# 3v3Regulator.net
KiCad netlist of a schematic drawn in Altium Designer
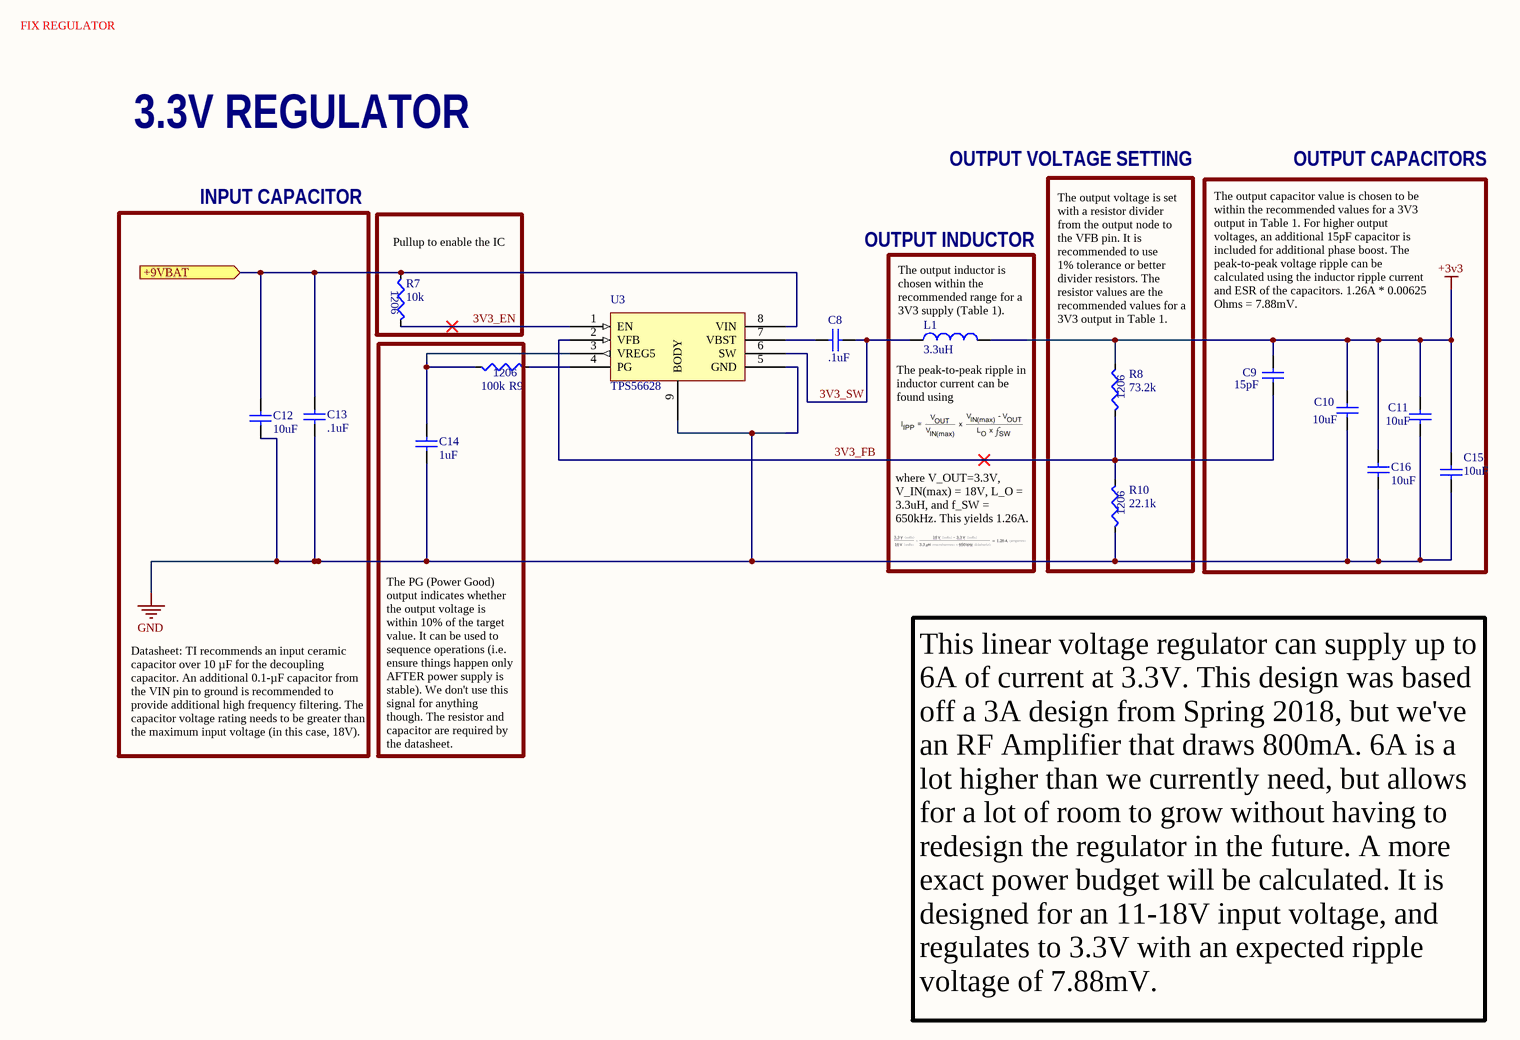
[diagram p0: 3v3Regulator.SchDoc]

(export (version "E")
  (design (tool "Eeschema 10.0.6"))
  (components
    (comp (ref "C8")
      (value ".1uF")
      (footprint "Capacitors:C1206")
      (description "CAP CER 0.1UF 50V C0G/NP0 1206")
      (fields (field (name "MADE BY") "Brennan Swanton") (field (name "REVIEWED BY") "Carter Allen"))
      (libsource (lib "Capacitors") (part "CL31B104KBCNNNC"))
    )
    (comp (ref "C9")
      (value "15pF")
      (footprint "C1206")
      (description "CAP CER 15PF 50V C0G/NP0 1206")
      (libsource (lib "Capacitors") (part "C1206C150K5GACTU"))
    )
    (comp (ref "C10")
      (value "10uF")
      (footprint "Capacitors:C1206")
      (description "CER 10UF 35V X7R 1206")
      (fields (field (name "MADE BY") "Brennan Swanton") (field (name "REVIEWED BY") "Carter Allen"))
      (libsource (lib "Capacitors") (part "CL31B106KLHNNNE"))
    )
    (comp (ref "C11")
      (value "10uF")
      (footprint "Capacitors:C1206")
      (description "CER 10UF 35V X7R 1206")
      (fields (field (name "MADE BY") "Brennan Swanton") (field (name "REVIEWED BY") "Carter Allen"))
      (libsource (lib "Capacitors") (part "CL31B106KLHNNNE"))
    )
    (comp (ref "C12")
      (value "10uF")
      (footprint "Capacitors:C1206")
      (description "CER 10UF 35V X7R 1206")
      (fields (field (name "MADE BY") "Brennan Swanton") (field (name "REVIEWED BY") "Carter Allen"))
      (libsource (lib "Capacitors") (part "CL31B106KLHNNNE"))
    )
    (comp (ref "C13")
      (value ".1uF")
      (footprint "Capacitors:C1206")
      (description "CAP CER 0.1UF 50V C0G/NP0 1206")
      (fields (field (name "MADE BY") "Brennan Swanton") (field (name "REVIEWED BY") "Carter Allen"))
      (libsource (lib "Capacitors") (part "CL31B104KBCNNNC"))
    )
    (comp (ref "C14")
      (value "1uF")
      (footprint "Capacitors:C1206")
      (description "CER 1UF 50V X7R 1206")
      (fields (field (name "MADE BY") "Brennan Swanton") (field (name "REVIEWED BY") "Carter Allen"))
      (libsource (lib "Capacitors") (part "CL31B105KBHNNNE"))
    )
    (comp (ref "C15")
      (value "10uF")
      (footprint "Capacitors:C1206")
      (description "CER 10UF 35V X7R 1206")
      (fields (field (name "MADE BY") "Brennan Swanton") (field (name "REVIEWED BY") "Carter Allen"))
      (libsource (lib "Capacitors") (part "CL31B106KLHNNNE"))
    )
    (comp (ref "C16")
      (value "10uF")
      (footprint "Capacitors:C1206")
      (description "CER 10UF 35V X7R 1206")
      (fields (field (name "MADE BY") "Brennan Swanton") (field (name "REVIEWED BY") "Carter Allen"))
      (libsource (lib "Capacitors") (part "CL31B106KLHNNNE"))
    )
    (comp (ref "L1")
      (value "3.3uH")
      (footprint "EATON_DR125")
      (description "Inductor 3.3uH 9.26A 20%")
      (libsource (lib "Inductors") (part "DR125-3R3-R"))
    )
    (comp (ref "R7")
      (value "10k")
      (footprint "Resistors:R1206")
      (description "10K OHM 1% 1/4W 1206")
      (fields (field (name "MADE BY") "Brennan Swanton") (field (name "REVIEWED BY") "Carter Allen"))
      (libsource (lib "Resistors") (part "ERJ-8ENF1002V"))
    )
    (comp (ref "R8")
      (value "73.2k")
      (footprint "R1206")
      (description "73.2K OHM 1% 1/4W 1206")
      (fields (field (name "MADE BY") "Raphael Navarro") (field (name "REVIEWED BY") "No one, yet"))
      (libsource (lib "Resistors") (part "ERJ-8ENF7322V"))
    )
    (comp (ref "R9")
      (value "100k")
      (footprint "Resistors:R1206")
      (description "100K OHM 1% 1/4W 1206")
      (fields (field (name "MADE BY") "Brennan Swanton") (field (name "REVIEWED BY") "Carter Allen"))
      (libsource (lib "Resistors") (part "ERJ-8ENF1003V"))
    )
    (comp (ref "R10")
      (value "22.1k")
      (footprint "R1206")
      (description "22.1K OHM 1% 1/4W 1206")
      (libsource (lib "Resistors") (part "ERJ-8ENF2212V"))
    )
    (comp (ref "U3")
      (value "TPS56628")
      (footprint "R-PDSO-G8")
      (description "Buck Regulator IC Adj. 6A 4.5V-18V Input")
      (libsource (lib "VoltageRegulators") (part "TPS56628"))
    )
  )
  (nets
    (net (code "1") (name "+3v3") (class "Default")
      (node (ref "C10") (pin "2") (pinfunction "2_2") (pintype "passive"))
      (node (ref "C11") (pin "2") (pinfunction "2_2") (pintype "passive"))
      (node (ref "C15") (pin "2") (pinfunction "2_2") (pintype "passive"))
      (node (ref "C16") (pin "2") (pinfunction "2_2") (pintype "passive"))
      (node (ref "C9") (pin "2") (pinfunction "2_2") (pintype "passive"))
      (node (ref "L1") (pin "2") (pinfunction "2_2") (pintype "passive"))
      (node (ref "R8") (pin "2") (pinfunction "2_2") (pintype "passive"))
    )
    (net (code "2") (name "/+9VBAT") (class "Default")
      (node (ref "C12") (pin "2") (pinfunction "2_2") (pintype "passive"))
      (node (ref "C13") (pin "2") (pinfunction "2_2") (pintype "passive"))
      (node (ref "R7") (pin "1") (pinfunction "1_1") (pintype "passive"))
      (node (ref "U3") (pin "8") (pinfunction "VIN_8") (pintype "power_in"))
    )
    (net (code "3") (name "/3V3_EN") (class "Default")
      (node (ref "R7") (pin "2") (pinfunction "2_2") (pintype "passive"))
      (node (ref "U3") (pin "1") (pinfunction "EN_1") (pintype "input"))
    )
    (net (code "4") (name "/3V3_FB") (class "Default")
      (node (ref "C9") (pin "1") (pinfunction "1_1") (pintype "passive"))
      (node (ref "R10") (pin "2") (pinfunction "2_2") (pintype "passive"))
      (node (ref "R8") (pin "1") (pinfunction "1_1") (pintype "passive"))
      (node (ref "U3") (pin "2") (pinfunction "VFB_2") (pintype "input"))
    )
    (net (code "5") (name "/3V3_SW") (class "Default")
      (node (ref "C8") (pin "1") (pinfunction "1_1") (pintype "passive"))
      (node (ref "L1") (pin "1") (pinfunction "1_1") (pintype "passive"))
      (node (ref "U3") (pin "6") (pinfunction "SW_6") (pintype "power_in"))
    )
    (net (code "6") (name "GND") (class "Default")
      (node (ref "C10") (pin "1") (pinfunction "1_1") (pintype "passive"))
      (node (ref "C11") (pin "1") (pinfunction "1_1") (pintype "passive"))
      (node (ref "C12") (pin "1") (pinfunction "1_1") (pintype "passive"))
      (node (ref "C13") (pin "1") (pinfunction "1_1") (pintype "passive"))
      (node (ref "C14") (pin "1") (pinfunction "1_1") (pintype "passive"))
      (node (ref "C15") (pin "1") (pinfunction "1_1") (pintype "passive"))
      (node (ref "C16") (pin "1") (pinfunction "1_1") (pintype "passive"))
      (node (ref "R10") (pin "1") (pinfunction "1_1") (pintype "passive"))
      (node (ref "U3") (pin "5") (pinfunction "GND_5") (pintype "power_in"))
      (node (ref "U3") (pin "9") (pinfunction "BODY_9") (pintype "power_in"))
    )
    (net (code "7") (name "Net-(U3-PG)") (class "Default")
      (node (ref "R9") (pin "2") (pinfunction "2_2") (pintype "passive"))
      (node (ref "U3") (pin "4") (pinfunction "PG_4") (pintype "open_collector"))
    )
    (net (code "8") (name "Net-(U3-VBST)") (class "Default")
      (node (ref "C8") (pin "2") (pinfunction "2_2") (pintype "passive"))
      (node (ref "U3") (pin "7") (pinfunction "VBST_7") (pintype "power_in"))
    )
    (net (code "9") (name "Net-(U3-VREG5)") (class "Default")
      (node (ref "C14") (pin "2") (pinfunction "2_2") (pintype "passive"))
      (node (ref "R9") (pin "1") (pinfunction "1_1") (pintype "passive"))
      (node (ref "U3") (pin "3") (pinfunction "VREG5_3") (pintype "output"))
    )
  )
)
